# teensy_audio_conn_sm_print.net
KiCad netlist of a schematic drawn in EAGLE
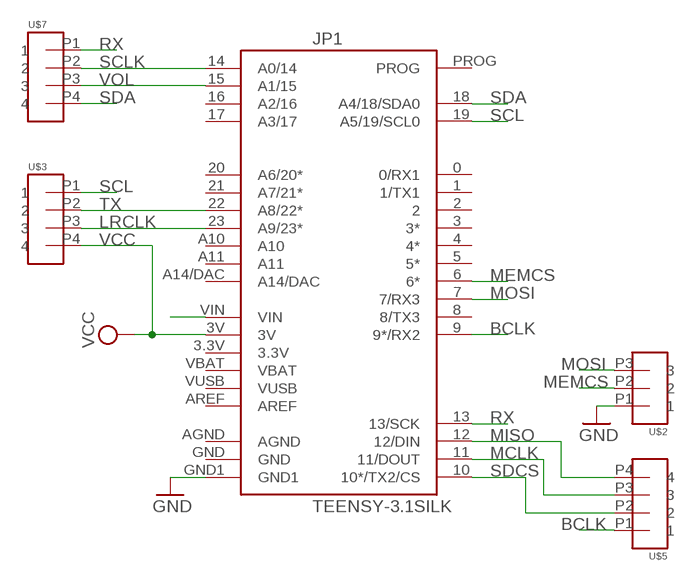
[diagram p0: schematic, sheet 1]

(export (version "E")
  (design (tool "Eeschema 10.0.6"))
  (components
    (comp (ref "JP1")
      (value "TEENSY-3.1SILK")
      (footprint "eagle-import:TEENSY-3.1")
      (libsource (lib "eagle-import") (part "TEENSY-3.1SILK"))
    )
    (comp (ref "U$2")
      (value "PTSM0,3-HH-2,5-SMD-R44")
      (footprint "eagle-import:M03_SMD_RIGHT")
      (libsource (lib "eagle-import") (part "PTSM0,3-HH-2,5-SMD-R44"))
    )
    (comp (ref "U$3")
      (value "PTSM0,4-HH-2,5-SMD-R44")
      (footprint "eagle-import:M04_SMD_RIGHT")
      (libsource (lib "eagle-import") (part "PTSM0,4-HH-2,5-SMD-R44"))
    )
    (comp (ref "U$5")
      (value "PTSM0,4-HH-2,5-SMD-R44")
      (footprint "eagle-import:M04_SMD_RIGHT")
      (libsource (lib "eagle-import") (part "PTSM0,4-HH-2,5-SMD-R44"))
    )
    (comp (ref "U$7")
      (value "PTSM0,4-HH-2,5-SMD-R44")
      (footprint "eagle-import:M04_SMD_RIGHT")
      (libsource (lib "eagle-import") (part "PTSM0,4-HH-2,5-SMD-R44"))
    )
  )
  (nets
    (net (code "1") (name "/BCLK") (class "Default")
      (node (ref "JP1") (pin "9") (pinfunction "9*/RX2_9") (pintype "bidirectional"))
      (node (ref "U$5") (pin "P1") (pinfunction "1_P1") (pintype "bidirectional"))
    )
    (net (code "2") (name "/LRCLK") (class "Default")
      (node (ref "JP1") (pin "23") (pinfunction "A9/23*_23") (pintype "bidirectional"))
      (node (ref "U$3") (pin "P3") (pinfunction "3_P3") (pintype "bidirectional"))
    )
    (net (code "3") (name "/MCLK") (class "Default")
      (node (ref "JP1") (pin "11") (pinfunction "11/DOUT_11") (pintype "bidirectional"))
      (node (ref "U$5") (pin "P3") (pinfunction "3_P3") (pintype "bidirectional"))
    )
    (net (code "4") (name "/MEMCS") (class "Default")
      (node (ref "JP1") (pin "6") (pinfunction "6*_6") (pintype "bidirectional"))
      (node (ref "U$2") (pin "P2") (pinfunction "2_P2") (pintype "bidirectional"))
    )
    (net (code "5") (name "/MISO") (class "Default")
      (node (ref "JP1") (pin "12") (pinfunction "12/DIN_12") (pintype "bidirectional"))
      (node (ref "U$5") (pin "P4") (pinfunction "4_P4") (pintype "bidirectional"))
    )
    (net (code "6") (name "/MOSI") (class "Default")
      (node (ref "JP1") (pin "7") (pinfunction "7/RX3_7") (pintype "bidirectional"))
      (node (ref "U$2") (pin "P3") (pinfunction "3_P3") (pintype "bidirectional"))
    )
    (net (code "7") (name "/RX") (class "Default")
      (node (ref "JP1") (pin "13") (pinfunction "13/SCK_13") (pintype "bidirectional"))
      (node (ref "U$7") (pin "P1") (pinfunction "1_P1") (pintype "bidirectional"))
    )
    (net (code "8") (name "/SCL") (class "Default")
      (node (ref "JP1") (pin "19") (pinfunction "A5/19/SCL0_19") (pintype "bidirectional"))
      (node (ref "U$3") (pin "P1") (pinfunction "1_P1") (pintype "bidirectional"))
    )
    (net (code "9") (name "/SCLK") (class "Default")
      (node (ref "JP1") (pin "14") (pinfunction "A0/14_14") (pintype "bidirectional"))
      (node (ref "U$7") (pin "P2") (pinfunction "2_P2") (pintype "bidirectional"))
    )
    (net (code "10") (name "/SDA") (class "Default")
      (node (ref "JP1") (pin "18") (pinfunction "A4/18/SDA0_18") (pintype "bidirectional"))
      (node (ref "U$7") (pin "P4") (pinfunction "4_P4") (pintype "bidirectional"))
    )
    (net (code "11") (name "/SDCS") (class "Default")
      (node (ref "JP1") (pin "10") (pinfunction "10*/TX2/CS_10") (pintype "bidirectional"))
      (node (ref "U$5") (pin "P2") (pinfunction "2_P2") (pintype "bidirectional"))
    )
    (net (code "12") (name "/TX") (class "Default")
      (node (ref "JP1") (pin "22") (pinfunction "A8/22*_22") (pintype "bidirectional"))
      (node (ref "U$3") (pin "P2") (pinfunction "2_P2") (pintype "bidirectional"))
    )
    (net (code "13") (name "/VOL") (class "Default")
      (node (ref "JP1") (pin "15") (pinfunction "A1/15_15") (pintype "bidirectional"))
      (node (ref "U$7") (pin "P3") (pinfunction "3_P3") (pintype "bidirectional"))
    )
    (net (code "14") (name "GND") (class "Default")
      (node (ref "JP1") (pin "GND1") (pinfunction "GND1_GND1") (pintype "bidirectional"))
      (node (ref "U$2") (pin "P1") (pinfunction "1_P1") (pintype "bidirectional"))
    )
    (net (code "15") (name "VCC") (class "Default")
      (node (ref "JP1") (pin "3V") (pinfunction "3V_3V") (pintype "bidirectional"))
      (node (ref "U$3") (pin "P4") (pinfunction "4_P4") (pintype "bidirectional"))
    )
    (net (code "16") (name "unconnected-(JP1-0{slash}RX1-Pad0)") (class "Default")
      (node (ref "JP1") (pin "0") (pinfunction "0/RX1_0") (pintype "bidirectional"))
    )
    (net (code "17") (name "unconnected-(JP1-1{slash}TX1-Pad1)") (class "Default")
      (node (ref "JP1") (pin "1") (pinfunction "1/TX1_1") (pintype "bidirectional"))
    )
    (net (code "18") (name "unconnected-(JP1-3*-Pad3)") (class "Default")
      (node (ref "JP1") (pin "3") (pinfunction "3*_3") (pintype "bidirectional"))
    )
    (net (code "19") (name "unconnected-(JP1-4*-Pad4)") (class "Default")
      (node (ref "JP1") (pin "4") (pinfunction "4*_4") (pintype "bidirectional"))
    )
    (net (code "20") (name "unconnected-(JP1-5*-Pad5)") (class "Default")
      (node (ref "JP1") (pin "5") (pinfunction "5*_5") (pintype "bidirectional"))
    )
    (net (code "21") (name "unconnected-(JP1-8{slash}TX3-Pad8)") (class "Default")
      (node (ref "JP1") (pin "8") (pinfunction "8/TX3_8") (pintype "bidirectional"))
    )
    (net (code "22") (name "unconnected-(JP1-A2{slash}16-Pad16)") (class "Default")
      (node (ref "JP1") (pin "16") (pinfunction "A2/16_16") (pintype "bidirectional"))
    )
    (net (code "23") (name "unconnected-(JP1-A3{slash}17-Pad17)") (class "Default")
      (node (ref "JP1") (pin "17") (pinfunction "A3/17_17") (pintype "bidirectional"))
    )
    (net (code "24") (name "unconnected-(JP1-A6{slash}20*-Pad20)") (class "Default")
      (node (ref "JP1") (pin "20") (pinfunction "A6/20*_20") (pintype "bidirectional"))
    )
    (net (code "25") (name "unconnected-(JP1-A7{slash}21*-Pad21)") (class "Default")
      (node (ref "JP1") (pin "21") (pinfunction "A7/21*_21") (pintype "bidirectional"))
    )
    (net (code "26") (name "unconnected-(JP1-Pad2)") (class "Default")
      (node (ref "JP1") (pin "2") (pinfunction "2_2") (pintype "bidirectional"))
    )
    (net (code "27") (name "unconnected-(JP1-Pad3.3V)") (class "Default")
      (node (ref "JP1") (pin "3.3V") (pinfunction "3.3V_3.3V") (pintype "bidirectional"))
    )
    (net (code "28") (name "unconnected-(JP1-PadA10)") (class "Default")
      (node (ref "JP1") (pin "A10") (pinfunction "A10_A10") (pintype "bidirectional"))
    )
    (net (code "29") (name "unconnected-(JP1-PadA11)") (class "Default")
      (node (ref "JP1") (pin "A11") (pinfunction "A11_A11") (pintype "bidirectional"))
    )
    (net (code "30") (name "unconnected-(JP1-PadA14{slash}DAC)") (class "Default")
      (node (ref "JP1") (pin "A14/DAC") (pinfunction "A14/DAC_A14/DAC") (pintype "bidirectional"))
    )
    (net (code "31") (name "unconnected-(JP1-PadAGND)") (class "Default")
      (node (ref "JP1") (pin "AGND") (pinfunction "AGND_AGND") (pintype "bidirectional"))
    )
    (net (code "32") (name "unconnected-(JP1-PadAREF)") (class "Default")
      (node (ref "JP1") (pin "AREF") (pinfunction "AREF_AREF") (pintype "bidirectional"))
    )
    (net (code "33") (name "unconnected-(JP1-PadGND)") (class "Default")
      (node (ref "JP1") (pin "GND") (pinfunction "GND_GND") (pintype "bidirectional"))
    )
    (net (code "34") (name "unconnected-(JP1-PadPROG)") (class "Default")
      (node (ref "JP1") (pin "PROG") (pinfunction "PROG_PROG") (pintype "bidirectional"))
    )
    (net (code "35") (name "unconnected-(JP1-PadVBAT)") (class "Default")
      (node (ref "JP1") (pin "VBAT") (pinfunction "VBAT_VBAT") (pintype "bidirectional"))
    )
    (net (code "36") (name "unconnected-(JP1-PadVIN)") (class "Default")
      (node (ref "JP1") (pin "VIN") (pinfunction "VIN_VIN") (pintype "bidirectional"))
    )
    (net (code "37") (name "unconnected-(JP1-PadVUSB)") (class "Default")
      (node (ref "JP1") (pin "VUSB") (pinfunction "VUSB_VUSB") (pintype "bidirectional"))
    )
  )
)
